# TestFanTachoPulseIn.net
KiCad netlist of a schematic drawn in EAGLE
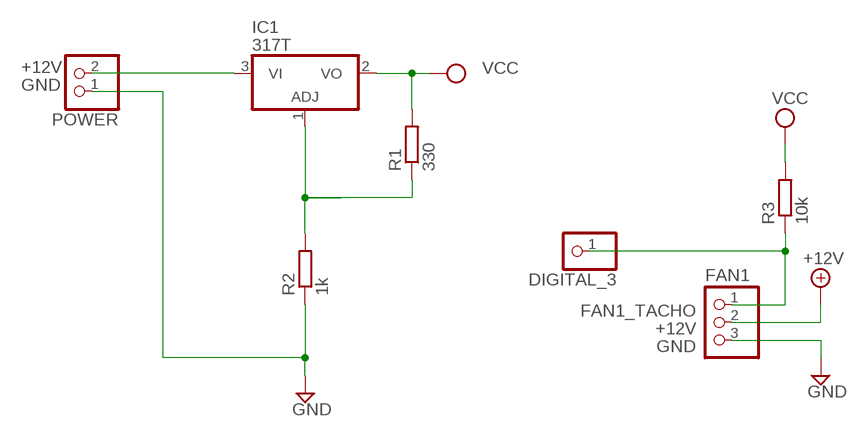
[diagram p0: schematic, sheet 1]

(export (version "E")
  (design (tool "Eeschema 10.0.6"))
  (components
    (comp (ref "DIGITAL_3")
      (value "PINHD-1X1")
      (footprint "eagle-import:1X01")
      (libsource (lib "eagle-import") (part "PINHD-1X1"))
    )
    (comp (ref "FAN1")
      (value "PINHD-1X3")
      (footprint "eagle-import:1X03")
      (libsource (lib "eagle-import") (part "PINHD-1X3"))
    )
    (comp (ref "IC1")
      (value "317T")
      (footprint "eagle-import:TO220H")
      (libsource (lib "eagle-import") (part "317T"))
    )
    (comp (ref "POWER")
      (value "PINHD-1X2")
      (footprint "eagle-import:1X02")
      (libsource (lib "eagle-import") (part "PINHD-1X2"))
    )
    (comp (ref "R1")
      (value "330")
      (footprint "eagle-import:0207_2V")
      (libsource (lib "eagle-import") (part "R-EU_0207/2V"))
    )
    (comp (ref "R2")
      (value "1k")
      (footprint "eagle-import:0207_12")
      (libsource (lib "eagle-import") (part "rcl_R-EU_0207/12"))
    )
    (comp (ref "R3")
      (value "10k")
      (footprint "eagle-import:0207_7")
      (libsource (lib "eagle-import") (part "rcl_R-EU_0207/7"))
    )
  )
  (nets
    (net (code "1") (name "+12V") (class "Default")
      (node (ref "FAN1") (pin "2") (pinfunction "2_2") (pintype "passive"))
      (node (ref "IC1") (pin "3") (pinfunction "VI_3") (pintype "input"))
      (node (ref "POWER") (pin "2") (pinfunction "2_2") (pintype "passive"))
    )
    (net (code "2") (name "/FAN1_TACHO") (class "Default")
      (node (ref "DIGITAL_3") (pin "1") (pinfunction "1_1") (pintype "passive"))
      (node (ref "FAN1") (pin "1") (pinfunction "1_1") (pintype "passive"))
      (node (ref "R3") (pin "1") (pinfunction "1_1") (pintype "passive"))
    )
    (net (code "3") (name "GND") (class "Default")
      (node (ref "FAN1") (pin "3") (pinfunction "3_3") (pintype "passive"))
      (node (ref "POWER") (pin "1") (pinfunction "1_1") (pintype "passive"))
      (node (ref "R2") (pin "1") (pinfunction "1_1") (pintype "passive"))
    )
    (net (code "4") (name "Net-(IC1-ADJ)") (class "Default")
      (node (ref "IC1") (pin "1") (pinfunction "ADJ_1") (pintype "input"))
      (node (ref "R1") (pin "1") (pinfunction "1_1") (pintype "passive"))
      (node (ref "R2") (pin "2") (pinfunction "2_2") (pintype "passive"))
    )
    (net (code "5") (name "VCC") (class "Default")
      (node (ref "IC1") (pin "2") (pinfunction "VO_2") (pintype "passive"))
      (node (ref "R1") (pin "2") (pinfunction "2_2") (pintype "passive"))
      (node (ref "R3") (pin "2") (pinfunction "2_2") (pintype "passive"))
    )
  )
)
